# MCU_64.net
KiCad netlist of a schematic drawn in Altium Designer
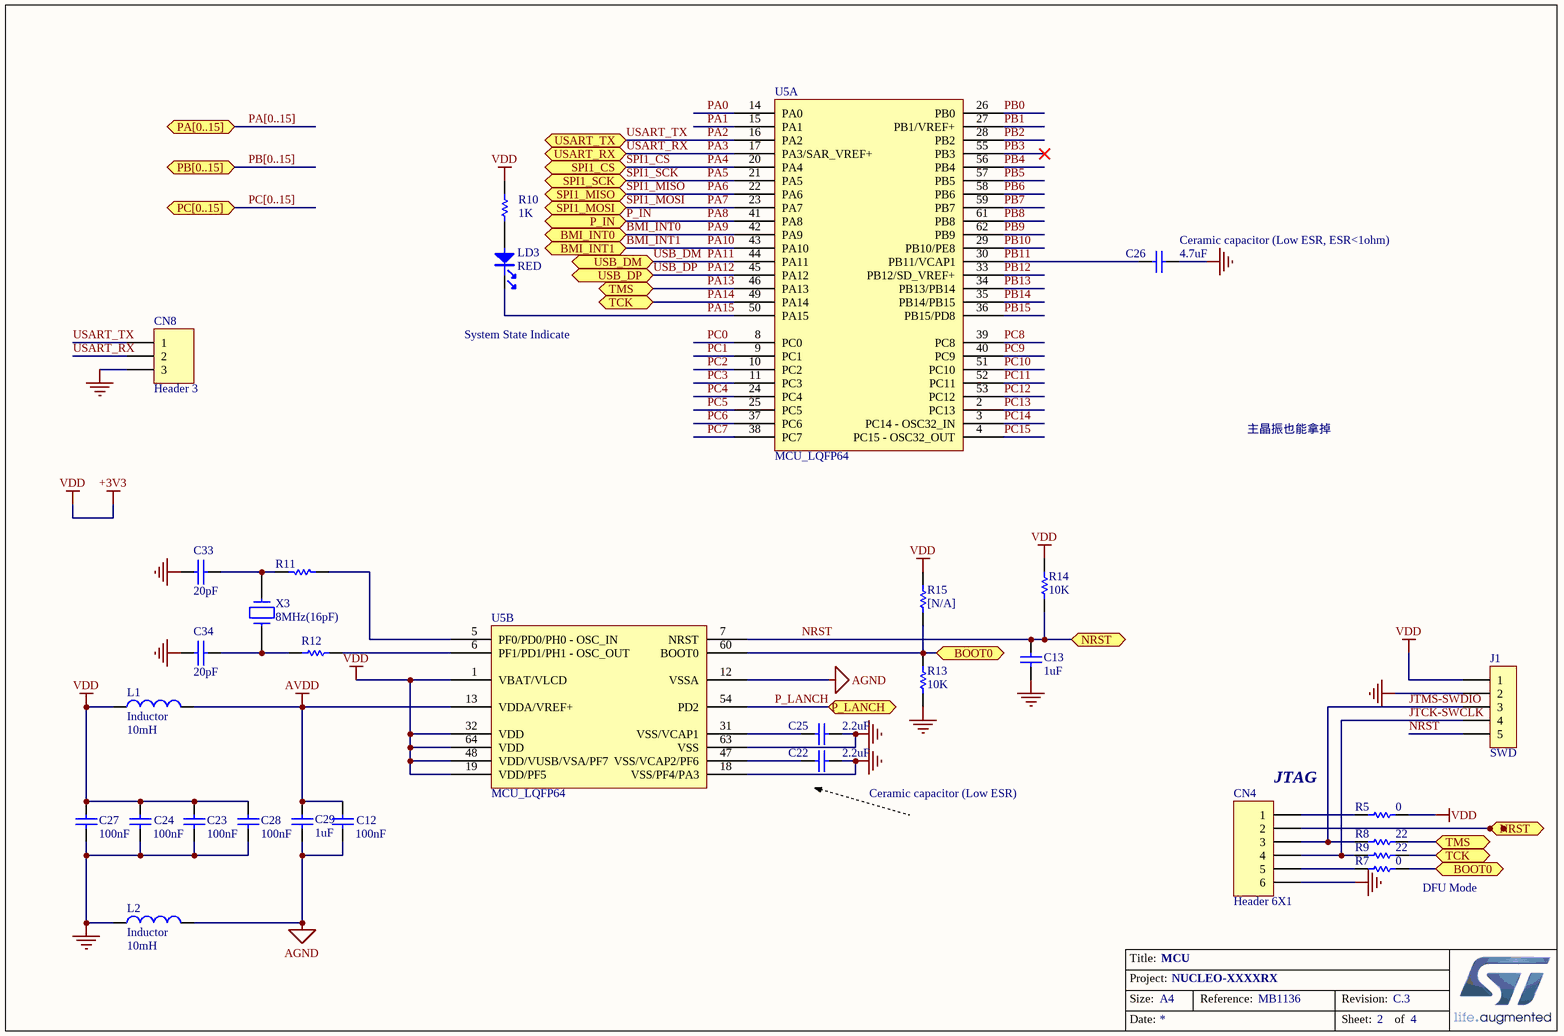
[diagram p0: MCU_64.SchDoc]

(export (version "E")
  (design (tool "Eeschema 10.0.6"))
  (components
    (comp (ref "C12")
      (value "100nF")
      (footprint "0603C")
      (description "Capacitor")
      (fields (field (name "PUBLISHER") "Altium Limited"))
      (libsource (lib "Miscellaneous Devices") (part "Cap"))
    )
    (comp (ref "C13")
      (value "1uF")
      (footprint "0603C")
      (description "0603  X5R 1礔")
      (fields (field (name "TOLERANCE") "10%"))
      (libsource (lib "MB963_1") (part "CAP SMD 0603  X5R 1礔 25V 10%"))
    )
    (comp (ref "C22")
      (value "2.2uF")
      (footprint "C-0805")
      (description "Capacitor,2.2uF,16V, X7R,10%,0805,YAGEO")
      (libsource (lib "MCD_TOOLS") (part "Cap_2.2uF_X7R_10%_0805"))
    )
    (comp (ref "C23")
      (value "100nF")
      (footprint "0603C")
      (description "Capacitor")
      (fields (field (name "PUBLISHER") "Altium Limited"))
      (libsource (lib "Miscellaneous Devices") (part "Cap"))
    )
    (comp (ref "C24")
      (value "100nF")
      (footprint "0603C")
      (description "Capacitor")
      (fields (field (name "PUBLISHER") "Altium Limited"))
      (libsource (lib "Miscellaneous Devices") (part "Cap"))
    )
    (comp (ref "C25")
      (value "2.2uF")
      (footprint "C-0805")
      (description "Capacitor,2.2uF,16V, X7R,10%,0805,YAGEO")
      (libsource (lib "MCD_TOOLS") (part "Cap_2.2uF_X7R_10%_0805"))
    )
    (comp (ref "C26")
      (value "4.7uF")
      (footprint "C-0805")
      (description "Capacitor,4.7uF,25V, X7R,10%,1206,YAGEO")
      (libsource (lib "MCD_TOOLS") (part "Cap_2.2uF_X7R_10%_0805"))
    )
    (comp (ref "C27")
      (value "100nF")
      (footprint "0603C")
      (description "Capacitor")
      (fields (field (name "PUBLISHER") "Altium Limited"))
      (libsource (lib "Miscellaneous Devices") (part "Cap"))
    )
    (comp (ref "C28")
      (value "100nF")
      (footprint "0603C")
      (description "Capacitor")
      (fields (field (name "PUBLISHER") "Altium Limited"))
      (libsource (lib "Miscellaneous Devices") (part "Cap"))
    )
    (comp (ref "C29")
      (value "1uF")
      (footprint "0603C")
      (description "0603  X5R 1礔")
      (fields (field (name "TOLERANCE") "10%"))
      (libsource (lib "MB963_1") (part "CAP SMD 0603  X5R 1礔 25V 10%"))
    )
    (comp (ref "C33")
      (value "20pF")
      (footprint "0603C")
      (description "Capacitor")
      (libsource (lib "*") (part "CAP"))
    )
    (comp (ref "C34")
      (value "20pF")
      (footprint "0603C")
      (description "Capacitor")
      (libsource (lib "*") (part "CAP"))
    )
    (comp (ref "CN4")
      (value "Header 6X1")
      (footprint "HDR1X6")
      (description "Header, 6-Pin")
      (fields (field (name "PUBLISHER") "Altium Limited"))
      (libsource (lib "Miscellaneous Connectors") (part "Header 6"))
    )
    (comp (ref "CN8")
      (value "Header 3")
      (footprint "HDR1X3")
      (description "Header, 3-Pin")
      (fields (field (name "PUBLISHER") "Altium Limited"))
      (libsource (lib "Miscellaneous Connectors") (part "Header 3"))
    )
    (comp (ref "J1")
      (value "SWD")
      (footprint "HDR1X5")
      (description "Connector")
      (libsource (lib "*") (part "CON5"))
    )
    (comp (ref "L1")
      (value "Inductor")
      (footprint "0603R")
      (fields (field (name "ALTIUM_VALUE") "10mH") (field (name "PUBLISHER") "Altium Limited"))
      (libsource (lib "Miscellaneous Devices") (part "Inductor"))
    )
    (comp (ref "L2")
      (value "Inductor")
      (footprint "0603R")
      (fields (field (name "ALTIUM_VALUE") "10mH") (field (name "PUBLISHER") "Altium Limited"))
      (libsource (lib "Miscellaneous Devices") (part "Inductor"))
    )
    (comp (ref "LD3") (value "RED") (footprint "0603D") (libsource (lib "MB963_1") (part "PHOTO")))
    (comp (ref "R5")
      (value "0")
      (footprint "0603R")
      (description "Resistor 0402 / 0603 / 0805")
      (libsource (lib "") (part "Res1_2"))
    )
    (comp (ref "R7")
      (value "0")
      (footprint "0603R")
      (description "Resistor 0402 / 0603 / 0805")
      (libsource (lib "") (part "Res1_2"))
    )
    (comp (ref "R8")
      (value "22")
      (footprint "0603R")
      (description "Resistor 0402 / 0603 / 0805")
      (libsource (lib "") (part "Res1_2"))
    )
    (comp (ref "R9")
      (value "22")
      (footprint "0603R")
      (description "Resistor 0402 / 0603 / 0805")
      (libsource (lib "") (part "Res1_2"))
    )
    (comp (ref "R10")
      (value "1K")
      (footprint "0603R")
      (description "Resistor 0402 / 0603 / 0805")
      (libsource (lib "MCD_TOOLS") (part "Resistor_ST"))
    )
    (comp (ref "R11")
      (value "~")
      (footprint "0603R")
      (description "Resistor")
      (fields (field (name "PUBLISHER") "Altium Limited"))
      (libsource (lib "") (part "Res1_1"))
    )
    (comp (ref "R12")
      (value "~")
      (footprint "0603R")
      (description "Resistor")
      (fields (field (name "PUBLISHER") "Altium Limited"))
      (libsource (lib "Miscellaneous Devices") (part "Res1"))
    )
    (comp (ref "R13")
      (value "10K")
      (footprint "0603R")
      (description "Resistor")
      (fields (field (name "PUBLISHER") "Altium Limited"))
      (libsource (lib "Miscellaneous Devices") (part "res1"))
    )
    (comp (ref "R14")
      (value "10K")
      (footprint "0603R")
      (description "Resistor")
      (fields (field (name "PUBLISHER") "Altium Limited"))
      (libsource (lib "Miscellaneous Devices") (part "res1"))
    )
    (comp (ref "R15")
      (value "[N/A]")
      (footprint "0603R")
      (description "Resistor")
      (fields (field (name "PUBLISHER") "Altium Limited"))
      (libsource (lib "Miscellaneous Devices") (part "res1"))
    )
    (comp (ref "U5")
      (value "MCU_LQFP64")
      (footprint "LQFP64")
      (libsource (lib "Nucleo_64") (part "MCU_LQFP64"))
    )
    (comp (ref "X3")
      (value "8MHz(16pF)")
      (footprint "X-1105/A-JL")
      (description "Crystal")
      (libsource (lib "*") (part "CRYSTAL"))
    )
  )
  (nets
    (net (code "1") (name "+3V3") (class "Default")
      (node (ref "C23") (pin "1") (pinfunction "1_1") (pintype "passive"))
      (node (ref "C24") (pin "1") (pinfunction "1_1") (pintype "passive"))
      (node (ref "C27") (pin "1") (pinfunction "1_1") (pintype "passive"))
      (node (ref "C28") (pin "1") (pinfunction "1_1") (pintype "passive"))
      (node (ref "J1") (pin "1") (pinfunction "1_1") (pintype "passive"))
      (node (ref "L1") (pin "1") (pinfunction "1_1") (pintype "passive"))
      (node (ref "R10") (pin "2") (pinfunction "2_2") (pintype "passive"))
      (node (ref "R14") (pin "1") (pinfunction "1_1") (pintype "passive"))
      (node (ref "R15") (pin "1") (pinfunction "1_1") (pintype "passive"))
      (node (ref "R5") (pin "2") (pinfunction "2_2") (pintype "passive"))
      (node (ref "U5") (pin "1") (pinfunction "VBAT/VLCD_1") (pintype "passive"))
      (node (ref "U5") (pin "19") (pinfunction "VDD/PF5_19") (pintype "passive"))
      (node (ref "U5") (pin "32") (pinfunction "VDD_32") (pintype "passive"))
      (node (ref "U5") (pin "48") (pinfunction "VDD/VUSB/VSA/PF7_48") (pintype "passive"))
      (node (ref "U5") (pin "64") (pinfunction "VDD_64") (pintype "passive"))
    )
    (net (code "2") (name "/BOOT0") (class "Default")
      (node (ref "R13") (pin "1") (pinfunction "1_1") (pintype "passive"))
      (node (ref "R15") (pin "2") (pinfunction "2_2") (pintype "passive"))
      (node (ref "R7") (pin "2") (pinfunction "2_2") (pintype "passive"))
      (node (ref "U5") (pin "60") (pinfunction "BOOT0_60") (pintype "passive"))
    )
    (net (code "3") (name "/JTCK-SWCLK") (class "Default")
      (node (ref "CN4") (pin "4") (pinfunction "4_4") (pintype "passive"))
      (node (ref "J1") (pin "4") (pinfunction "4_4") (pintype "passive"))
      (node (ref "R9") (pin "1") (pinfunction "1_1") (pintype "passive"))
    )
    (net (code "4") (name "/JTMS-SWDIO") (class "Default")
      (node (ref "CN4") (pin "3") (pinfunction "3_3") (pintype "passive"))
      (node (ref "J1") (pin "3") (pinfunction "3_3") (pintype "passive"))
      (node (ref "R8") (pin "1") (pinfunction "1_1") (pintype "passive"))
    )
    (net (code "5") (name "/NRST") (class "Default")
      (node (ref "C13") (pin "1") (pinfunction "1_1") (pintype "passive"))
      (node (ref "CN4") (pin "2") (pinfunction "2_2") (pintype "passive"))
      (node (ref "J1") (pin "5") (pinfunction "5_5") (pintype "passive"))
      (node (ref "R14") (pin "2") (pinfunction "2_2") (pintype "passive"))
      (node (ref "U5") (pin "7") (pinfunction "NRST_7") (pintype "passive"))
    )
    (net (code "6") (name "/PA0") (class "Default")
      (node (ref "U5") (pin "14") (pinfunction "PA0_14") (pintype "passive"))
    )
    (net (code "7") (name "/PA1") (class "Default")
      (node (ref "U5") (pin "15") (pinfunction "PA1_15") (pintype "passive"))
    )
    (net (code "8") (name "/PA2") (class "Default")
      (node (ref "CN8") (pin "1") (pinfunction "1_1") (pintype "passive"))
      (node (ref "U5") (pin "16") (pinfunction "PA2_16") (pintype "passive"))
    )
    (net (code "9") (name "/PA3") (class "Default")
      (node (ref "CN8") (pin "2") (pinfunction "2_2") (pintype "passive"))
      (node (ref "U5") (pin "17") (pinfunction "PA3/SAR_VREF+_17") (pintype "passive"))
    )
    (net (code "10") (name "/PA4") (class "Default")
      (node (ref "U5") (pin "20") (pinfunction "PA4_20") (pintype "passive"))
    )
    (net (code "11") (name "/PA5") (class "Default")
      (node (ref "U5") (pin "21") (pinfunction "PA5_21") (pintype "passive"))
    )
    (net (code "12") (name "/PA6") (class "Default")
      (node (ref "U5") (pin "22") (pinfunction "PA6_22") (pintype "passive"))
    )
    (net (code "13") (name "/PA7") (class "Default")
      (node (ref "U5") (pin "23") (pinfunction "PA7_23") (pintype "passive"))
    )
    (net (code "14") (name "/PA8") (class "Default")
      (node (ref "U5") (pin "41") (pinfunction "PA8_41") (pintype "passive"))
    )
    (net (code "15") (name "/PA9") (class "Default")
      (node (ref "U5") (pin "42") (pinfunction "PA9_42") (pintype "passive"))
    )
    (net (code "16") (name "/PA10") (class "Default")
      (node (ref "U5") (pin "43") (pinfunction "PA10_43") (pintype "passive"))
    )
    (net (code "17") (name "/PA11") (class "Default")
      (node (ref "U5") (pin "44") (pinfunction "PA11_44") (pintype "passive"))
    )
    (net (code "18") (name "/PA12") (class "Default")
      (node (ref "U5") (pin "45") (pinfunction "PA12_45") (pintype "passive"))
    )
    (net (code "19") (name "/PA13") (class "Default")
      (node (ref "R8") (pin "2") (pinfunction "2_2") (pintype "passive"))
      (node (ref "U5") (pin "46") (pinfunction "PA13_46") (pintype "passive"))
    )
    (net (code "20") (name "/PA14") (class "Default")
      (node (ref "R9") (pin "2") (pinfunction "2_2") (pintype "passive"))
      (node (ref "U5") (pin "49") (pinfunction "PA14_49") (pintype "passive"))
    )
    (net (code "21") (name "/PA15") (class "Default")
      (node (ref "LD3") (pin "2") (pintype "passive"))
      (node (ref "U5") (pin "50") (pinfunction "PA15_50") (pintype "passive"))
    )
    (net (code "23") (name "/PB0") (class "Default")
      (node (ref "U5") (pin "26") (pinfunction "PB0_26") (pintype "passive"))
    )
    (net (code "24") (name "/PB1") (class "Default")
      (node (ref "U5") (pin "27") (pinfunction "PB1/VREF+_27") (pintype "passive"))
    )
    (net (code "25") (name "/PB2") (class "Default")
      (node (ref "U5") (pin "28") (pinfunction "PB2_28") (pintype "passive"))
    )
    (net (code "26") (name "/PB3") (class "Default")
      (node (ref "U5") (pin "55") (pinfunction "PB3_55") (pintype "passive+no_connect"))
    )
    (net (code "27") (name "/PB4") (class "Default")
      (node (ref "U5") (pin "56") (pinfunction "PB4_56") (pintype "passive"))
    )
    (net (code "28") (name "/PB5") (class "Default")
      (node (ref "U5") (pin "57") (pinfunction "PB5_57") (pintype "passive"))
    )
    (net (code "29") (name "/PB6") (class "Default")
      (node (ref "U5") (pin "58") (pinfunction "PB6_58") (pintype "passive"))
    )
    (net (code "30") (name "/PB7") (class "Default")
      (node (ref "U5") (pin "59") (pinfunction "PB7_59") (pintype "passive"))
    )
    (net (code "31") (name "/PB8") (class "Default")
      (node (ref "U5") (pin "61") (pinfunction "PB8_61") (pintype "passive"))
    )
    (net (code "32") (name "/PB9") (class "Default")
      (node (ref "U5") (pin "62") (pinfunction "PB9_62") (pintype "passive"))
    )
    (net (code "33") (name "/PB10") (class "Default")
      (node (ref "U5") (pin "29") (pinfunction "PB10/PE8_29") (pintype "passive"))
    )
    (net (code "34") (name "/PB11") (class "Default")
      (node (ref "C26") (pin "1") (pinfunction "1_1") (pintype "passive"))
      (node (ref "U5") (pin "30") (pinfunction "PB11/VCAP1_30") (pintype "passive"))
    )
    (net (code "35") (name "/PB12") (class "Default")
      (node (ref "U5") (pin "33") (pinfunction "PB12/SD_VREF+_33") (pintype "passive"))
    )
    (net (code "36") (name "/PB13") (class "Default")
      (node (ref "U5") (pin "34") (pinfunction "PB13/PB14_34") (pintype "passive"))
    )
    (net (code "37") (name "/PB14") (class "Default")
      (node (ref "U5") (pin "35") (pinfunction "PB14/PB15_35") (pintype "passive"))
    )
    (net (code "38") (name "/PB15") (class "Default")
      (node (ref "U5") (pin "36") (pinfunction "PB15/PD8_36") (pintype "passive"))
    )
    (net (code "40") (name "/PC0") (class "Default")
      (node (ref "U5") (pin "8") (pinfunction "PC0_8") (pintype "passive"))
    )
    (net (code "41") (name "/PC1") (class "Default")
      (node (ref "U5") (pin "9") (pinfunction "PC1_9") (pintype "passive"))
    )
    (net (code "42") (name "/PC2") (class "Default")
      (node (ref "U5") (pin "10") (pinfunction "PC2_10") (pintype "passive"))
    )
    (net (code "43") (name "/PC3") (class "Default")
      (node (ref "U5") (pin "11") (pinfunction "PC3_11") (pintype "passive"))
    )
    (net (code "44") (name "/PC4") (class "Default")
      (node (ref "U5") (pin "24") (pinfunction "PC4_24") (pintype "passive"))
    )
    (net (code "45") (name "/PC5") (class "Default")
      (node (ref "U5") (pin "25") (pinfunction "PC5_25") (pintype "passive"))
    )
    (net (code "46") (name "/PC6") (class "Default")
      (node (ref "U5") (pin "37") (pinfunction "PC6_37") (pintype "passive"))
    )
    (net (code "47") (name "/PC7") (class "Default")
      (node (ref "U5") (pin "38") (pinfunction "PC7_38") (pintype "passive"))
    )
    (net (code "48") (name "/PC8") (class "Default")
      (node (ref "U5") (pin "39") (pinfunction "PC8_39") (pintype "passive"))
    )
    (net (code "49") (name "/PC9") (class "Default")
      (node (ref "U5") (pin "40") (pinfunction "PC9_40") (pintype "passive"))
    )
    (net (code "50") (name "/PC10") (class "Default")
      (node (ref "U5") (pin "51") (pinfunction "PC10_51") (pintype "passive"))
    )
    (net (code "51") (name "/PC11") (class "Default")
      (node (ref "U5") (pin "52") (pinfunction "PC11_52") (pintype "passive"))
    )
    (net (code "52") (name "/PC12") (class "Default")
      (node (ref "U5") (pin "53") (pinfunction "PC12_53") (pintype "passive"))
    )
    (net (code "53") (name "/PC13") (class "Default")
      (node (ref "U5") (pin "2") (pinfunction "PC13_2") (pintype "passive"))
    )
    (net (code "54") (name "/PC14") (class "Default")
      (node (ref "U5") (pin "3") (pinfunction "PC14_-_OSC32_IN_3") (pintype "passive"))
    )
    (net (code "55") (name "/PC15") (class "Default")
      (node (ref "U5") (pin "4") (pinfunction "PC15_-_OSC32_OUT_4") (pintype "passive"))
    )
    (net (code "57") (name "/P_LANCH") (class "Default")
      (node (ref "U5") (pin "54") (pinfunction "PD2_54") (pintype "passive"))
    )
    (net (code "58") (name "AGND") (class "Default")
      (node (ref "C12") (pin "2") (pinfunction "2_2") (pintype "passive"))
      (node (ref "C29") (pin "2") (pinfunction "2_2") (pintype "passive"))
      (node (ref "L2") (pin "2") (pinfunction "2_2") (pintype "passive"))
      (node (ref "U5") (pin "12") (pinfunction "VSSA_12") (pintype "passive"))
    )
    (net (code "59") (name "AVDD") (class "Default")
      (node (ref "C12") (pin "1") (pinfunction "1_1") (pintype "passive"))
      (node (ref "C29") (pin "1") (pinfunction "1_1") (pintype "passive"))
      (node (ref "L1") (pin "2") (pinfunction "2_2") (pintype "passive"))
      (node (ref "U5") (pin "13") (pinfunction "VDDA/VREF+_13") (pintype "passive"))
    )
    (net (code "60") (name "GND") (class "Default")
      (node (ref "C13") (pin "2") (pinfunction "2_2") (pintype "passive"))
      (node (ref "C22") (pin "2") (pinfunction "2_2") (pintype "passive"))
      (node (ref "C23") (pin "2") (pinfunction "2_2") (pintype "passive"))
      (node (ref "C24") (pin "2") (pinfunction "2_2") (pintype "passive"))
      (node (ref "C25") (pin "2") (pinfunction "2_2") (pintype "passive"))
      (node (ref "C26") (pin "2") (pinfunction "2_2") (pintype "passive"))
      (node (ref "C27") (pin "2") (pinfunction "2_2") (pintype "passive"))
      (node (ref "C28") (pin "2") (pinfunction "2_2") (pintype "passive"))
      (node (ref "C33") (pin "2") (pinfunction "2_2") (pintype "passive"))
      (node (ref "C34") (pin "2") (pinfunction "2_2") (pintype "passive"))
      (node (ref "CN4") (pin "6") (pinfunction "6_6") (pintype "passive"))
      (node (ref "CN8") (pin "3") (pinfunction "3_3") (pintype "passive"))
      (node (ref "J1") (pin "2") (pinfunction "2_2") (pintype "passive"))
      (node (ref "L2") (pin "1") (pinfunction "1_1") (pintype "passive"))
      (node (ref "R13") (pin "2") (pinfunction "2_2") (pintype "passive"))
      (node (ref "U5") (pin "18") (pinfunction "VSS/PF4/PA3_18") (pintype "passive"))
      (node (ref "U5") (pin "63") (pinfunction "VSS_63") (pintype "passive"))
    )
    (net (code "61") (name "Net-(C33-Pad1)") (class "Default")
      (node (ref "C33") (pin "1") (pinfunction "1_1") (pintype "passive"))
      (node (ref "R11") (pin "2") (pinfunction "2_2") (pintype "passive"))
      (node (ref "X3") (pin "2") (pinfunction "2_2") (pintype "passive"))
    )
    (net (code "62") (name "Net-(C34-Pad1)") (class "Default")
      (node (ref "C34") (pin "1") (pinfunction "1_1") (pintype "passive"))
      (node (ref "R12") (pin "2") (pinfunction "2_2") (pintype "passive"))
      (node (ref "X3") (pin "1") (pinfunction "1_1") (pintype "passive"))
    )
    (net (code "63") (name "Net-(CN4-Pad1)") (class "Default")
      (node (ref "CN4") (pin "1") (pinfunction "1_1") (pintype "passive"))
      (node (ref "R5") (pin "1") (pinfunction "1_1") (pintype "passive"))
    )
    (net (code "64") (name "Net-(CN4-Pad5)") (class "Default")
      (node (ref "CN4") (pin "5") (pinfunction "5_5") (pintype "passive"))
      (node (ref "R7") (pin "1") (pinfunction "1_1") (pintype "passive"))
    )
    (net (code "65") (name "Net-(LD3-Pad1)") (class "Default")
      (node (ref "LD3") (pin "1") (pintype "passive"))
      (node (ref "R10") (pin "1") (pinfunction "1_1") (pintype "passive"))
    )
    (net (code "66") (name "Net-(U5B-PF0{slash}PD0{slash}PH0_-_OSC_IN)") (class "Default")
      (node (ref "R11") (pin "1") (pinfunction "1_1") (pintype "passive"))
      (node (ref "U5") (pin "5") (pinfunction "PF0/PD0/PH0_-_OSC_IN_5") (pintype "passive"))
    )
    (net (code "67") (name "Net-(U5B-PF1{slash}PD1{slash}PH1_-_OSC_OUT)") (class "Default")
      (node (ref "R12") (pin "1") (pinfunction "1_1") (pintype "passive"))
      (node (ref "U5") (pin "6") (pinfunction "PF1/PD1/PH1_-_OSC_OUT_6") (pintype "passive"))
    )
    (net (code "68") (name "Net-(U5B-VSS{slash}VCAP1)") (class "Default")
      (node (ref "C25") (pin "1") (pinfunction "1_1") (pintype "passive"))
      (node (ref "U5") (pin "31") (pinfunction "VSS/VCAP1_31") (pintype "passive"))
    )
    (net (code "69") (name "Net-(U5B-VSS{slash}VCAP2{slash}PF6)") (class "Default")
      (node (ref "C22") (pin "1") (pinfunction "1_1") (pintype "passive"))
      (node (ref "U5") (pin "47") (pinfunction "VSS/VCAP2/PF6_47") (pintype "passive"))
    )
  )
)
